# STM32F303CBT6_BTN8962TA_V1_0.net
KiCad netlist of a schematic drawn in EAGLE
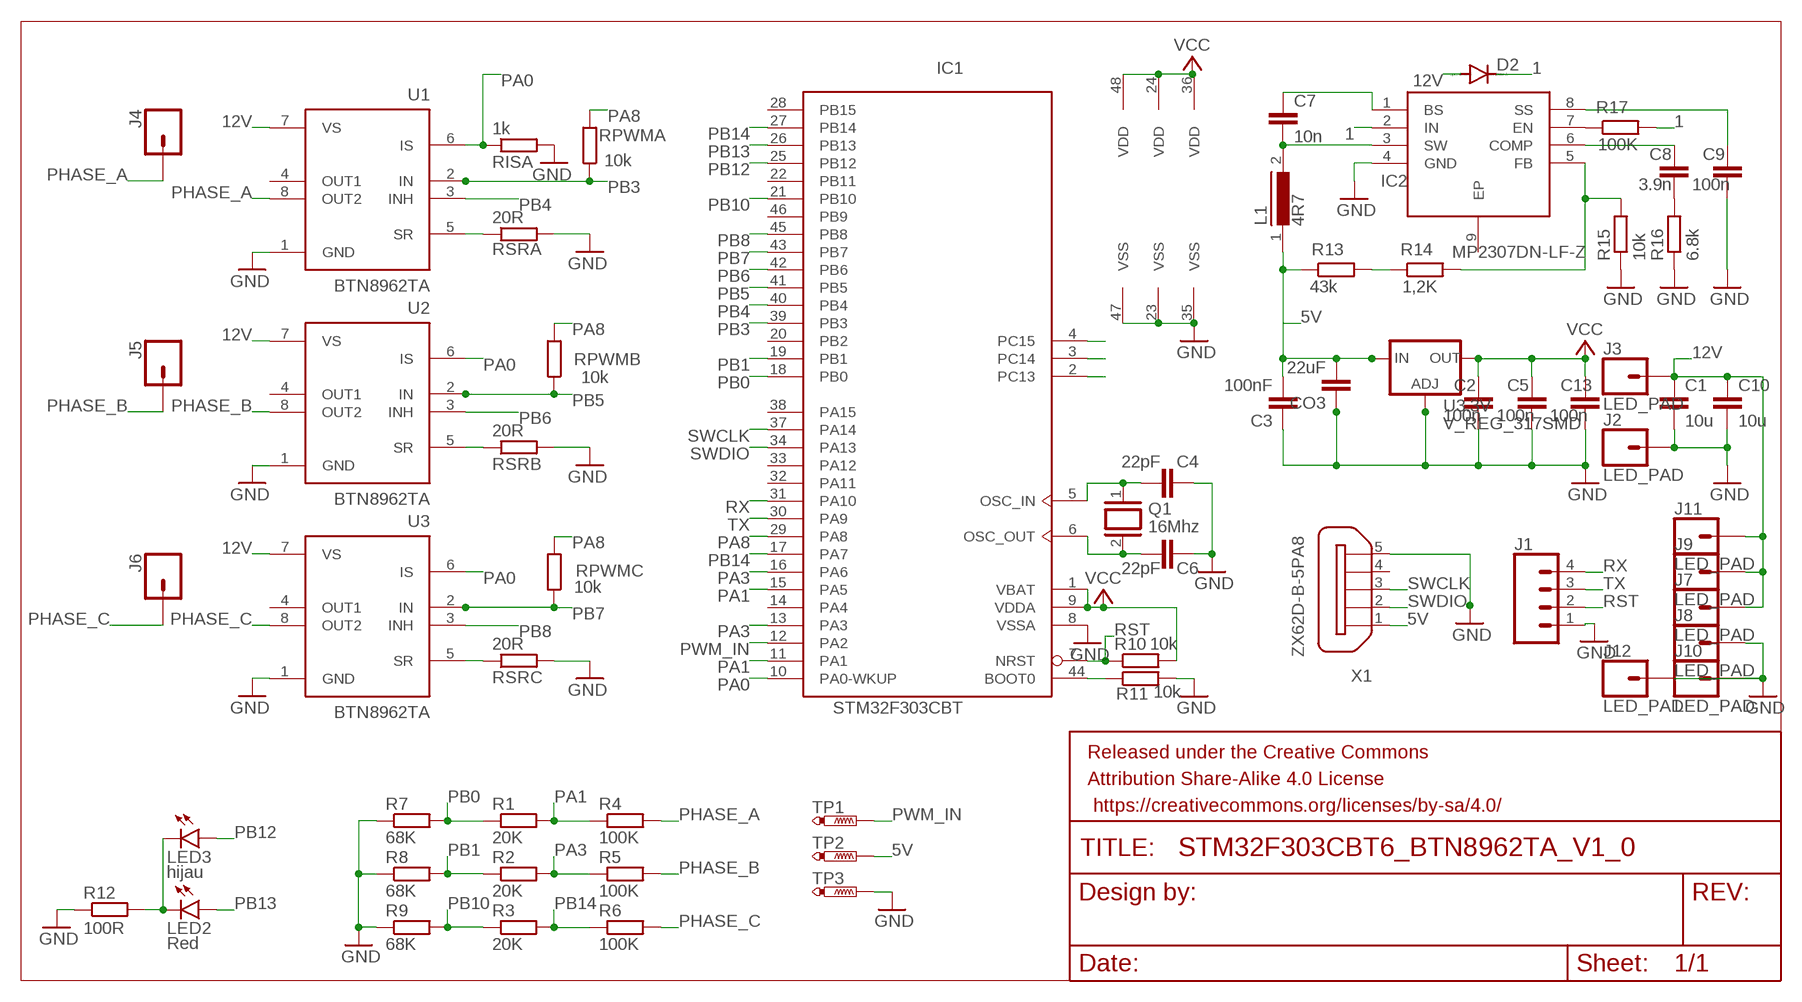
[diagram p0: schematic, sheet 1]

(export (version "E")
  (design (tool "Eeschema 10.0.6"))
  (components
    (comp (ref "C1")
      (value "10u")
      (footprint "eagle-import:C1206K")
      (libsource (lib "eagle-import") (part "rcl_334_C-EUC1206K"))
    )
    (comp (ref "C2")
      (value "100n")
      (footprint "eagle-import:C0603K")
      (libsource (lib "eagle-import") (part "rcl_334_C-EUC0603K"))
    )
    (comp (ref "C3")
      (value "100nF")
      (footprint "eagle-import:C0805")
      (libsource (lib "eagle-import") (part "C-EUC0805"))
    )
    (comp (ref "C4")
      (value "22pF")
      (footprint "eagle-import:C0805")
      (libsource (lib "eagle-import") (part "C-EUC0805"))
    )
    (comp (ref "C5")
      (value "100n")
      (footprint "eagle-import:C0603K")
      (libsource (lib "eagle-import") (part "rcl_334_C-EUC0603K"))
    )
    (comp (ref "C6")
      (value "22pF")
      (footprint "eagle-import:C0805")
      (libsource (lib "eagle-import") (part "C-EUC0805"))
    )
    (comp (ref "C7")
      (value "10n")
      (footprint "eagle-import:C0603K")
      (libsource (lib "eagle-import") (part "rcl_334_C-EUC0603K"))
    )
    (comp (ref "C8")
      (value "3.9n")
      (footprint "eagle-import:C0603K")
      (libsource (lib "eagle-import") (part "rcl_334_C-EUC0603K"))
    )
    (comp (ref "C9")
      (value "100n")
      (footprint "eagle-import:C0603K")
      (libsource (lib "eagle-import") (part "rcl_334_C-EUC0603K"))
    )
    (comp (ref "C10")
      (value "10u")
      (footprint "eagle-import:C1206K")
      (libsource (lib "eagle-import") (part "rcl_334_C-EUC1206K"))
    )
    (comp (ref "C13")
      (value "100n")
      (footprint "eagle-import:C0603K")
      (libsource (lib "eagle-import") (part "rcl_334_C-EUC0603K"))
    )
    (comp (ref "CO3")
      (value "22uF")
      (footprint "eagle-import:C0805")
      (libsource (lib "eagle-import") (part "C-EUC0805"))
    )
    (comp (ref "D2")
      (value "DIODE-SOD80C")
      (footprint "eagle-import:SOD80C")
      (libsource (lib "eagle-import") (part "DIODE-SOD80C"))
    )
    (comp (ref "FRAME1")
      (value "FRAME-LETTER")
      (footprint "eagle-import:CREATIVE_COMMONS")
      (libsource (lib "eagle-import") (part "FRAME-LETTER"))
    )
    (comp (ref "IC1")
      (value "STM32F303CBT")
      (footprint "eagle-import:LQFP48")
      (fields (field (name "SPICEPREFIX") "X"))
      (libsource (lib "eagle-import") (part "STM32F303CTB"))
    )
    (comp (ref "IC2")
      (value "MP2307DN-LF-Z")
      (footprint "eagle-import:SOIC127P600X170-9N")
      (fields (field (name "MOUSER_PART_NUMBER") "946-MP2307DNLFZ"))
      (libsource (lib "eagle-import") (part "MP2307DN-LF-Z"))
    )
    (comp (ref "J1")
      (value "CONN_04SMD2")
      (footprint "eagle-import:JST04_1MM_RA")
      (libsource (lib "eagle-import") (part "CONN_04SMD2"))
    )
    (comp (ref "J2")
      (value "LED_PAD")
      (footprint "eagle-import:CIRCULARPAD")
      (libsource (lib "eagle-import") (part "LED_PAD"))
    )
    (comp (ref "J3")
      (value "LED_PAD")
      (footprint "eagle-import:CIRCULARPAD")
      (libsource (lib "eagle-import") (part "LED_PAD"))
    )
    (comp (ref "J4")
      (value "CONN_01SNAP-MALE")
      (footprint "eagle-import:SNAP-MALE")
      (libsource (lib "eagle-import") (part "CONN_01SNAP-MALE"))
    )
    (comp (ref "J5")
      (value "CONN_01SNAP-MALE")
      (footprint "eagle-import:SNAP-MALE")
      (libsource (lib "eagle-import") (part "CONN_01SNAP-MALE"))
    )
    (comp (ref "J6")
      (value "CONN_01SNAP-MALE")
      (footprint "eagle-import:SNAP-MALE")
      (libsource (lib "eagle-import") (part "CONN_01SNAP-MALE"))
    )
    (comp (ref "J7")
      (value "LED_PAD")
      (footprint "eagle-import:CIRCULARPAD")
      (libsource (lib "eagle-import") (part "LED_PAD"))
    )
    (comp (ref "J8")
      (value "LED_PAD")
      (footprint "eagle-import:CIRCULARPAD")
      (libsource (lib "eagle-import") (part "LED_PAD"))
    )
    (comp (ref "J9")
      (value "LED_PAD")
      (footprint "eagle-import:CIRCULARPAD")
      (libsource (lib "eagle-import") (part "LED_PAD"))
    )
    (comp (ref "J10")
      (value "LED_PAD")
      (footprint "eagle-import:CIRCULARPAD")
      (libsource (lib "eagle-import") (part "LED_PAD"))
    )
    (comp (ref "J11")
      (value "LED_PAD")
      (footprint "eagle-import:CIRCULARPAD")
      (libsource (lib "eagle-import") (part "LED_PAD"))
    )
    (comp (ref "J12")
      (value "LED_PAD")
      (footprint "eagle-import:CIRCULARPAD")
      (libsource (lib "eagle-import") (part "LED_PAD"))
    )
    (comp (ref "L1")
      (value "4R7")
      (footprint "eagle-import:DR74")
      (libsource (lib "eagle-import") (part "DR74"))
    )
    (comp (ref "LED2")
      (value "Red")
      (footprint "eagle-import:CHIPLED_0805")
      (libsource (lib "eagle-import") (part "LEDCHIPLED_0805"))
    )
    (comp (ref "LED3")
      (value "hijau")
      (footprint "eagle-import:CHIPLED_0805")
      (libsource (lib "eagle-import") (part "LEDCHIPLED_0805"))
    )
    (comp (ref "Q1")
      (value "16Mhz")
      (footprint "eagle-import:QS")
      (libsource (lib "eagle-import") (part "XTAL/S"))
    )
    (comp (ref "R1")
      (value "20K")
      (footprint "eagle-import:R0805")
      (libsource (lib "eagle-import") (part "rcl_334_R-EU_R0805"))
    )
    (comp (ref "R2")
      (value "20K")
      (footprint "eagle-import:R0805")
      (libsource (lib "eagle-import") (part "rcl_334_R-EU_R0805"))
    )
    (comp (ref "R3")
      (value "20K")
      (footprint "eagle-import:R0805")
      (libsource (lib "eagle-import") (part "rcl_334_R-EU_R0805"))
    )
    (comp (ref "R4")
      (value "100K")
      (footprint "eagle-import:R0805")
      (libsource (lib "eagle-import") (part "rcl_334_R-EU_R0805"))
    )
    (comp (ref "R5")
      (value "100K")
      (footprint "eagle-import:R0805")
      (libsource (lib "eagle-import") (part "rcl_334_R-EU_R0805"))
    )
    (comp (ref "R6")
      (value "100K")
      (footprint "eagle-import:R0805")
      (libsource (lib "eagle-import") (part "rcl_334_R-EU_R0805"))
    )
    (comp (ref "R7")
      (value "68K")
      (footprint "eagle-import:R0805")
      (libsource (lib "eagle-import") (part "rcl_334_R-EU_R0805"))
    )
    (comp (ref "R8")
      (value "68K")
      (footprint "eagle-import:R0805")
      (libsource (lib "eagle-import") (part "rcl_334_R-EU_R0805"))
    )
    (comp (ref "R9")
      (value "68K")
      (footprint "eagle-import:R0805")
      (libsource (lib "eagle-import") (part "rcl_334_R-EU_R0805"))
    )
    (comp (ref "R10")
      (value "10k")
      (footprint "eagle-import:R0603")
      (libsource (lib "eagle-import") (part "rcl_334_R-EU_R0603"))
    )
    (comp (ref "R11")
      (value "10k")
      (footprint "eagle-import:R0603")
      (libsource (lib "eagle-import") (part "rcl_334_R-EU_R0603"))
    )
    (comp (ref "R12")
      (value "100R")
      (footprint "eagle-import:R0603")
      (libsource (lib "eagle-import") (part "rcl_334_R-EU_R0603"))
    )
    (comp (ref "R13")
      (value "43k")
      (footprint "eagle-import:R0603")
      (libsource (lib "eagle-import") (part "rcl_334_R-EU_R0603"))
    )
    (comp (ref "R14")
      (value "1,2K")
      (footprint "eagle-import:R0603")
      (libsource (lib "eagle-import") (part "rcl_334_R-EU_R0603"))
    )
    (comp (ref "R15")
      (value "10k")
      (footprint "eagle-import:R0603")
      (libsource (lib "eagle-import") (part "rcl_334_R-EU_R0603"))
    )
    (comp (ref "R16")
      (value "6.8k")
      (footprint "eagle-import:R0603")
      (libsource (lib "eagle-import") (part "rcl_334_R-EU_R0603"))
    )
    (comp (ref "R17")
      (value "100K")
      (footprint "eagle-import:R0603")
      (libsource (lib "eagle-import") (part "rcl_334_R-EU_R0603"))
    )
    (comp (ref "RISA")
      (value "1k")
      (footprint "eagle-import:R0805")
      (libsource (lib "eagle-import") (part "R-EU_R0805"))
    )
    (comp (ref "RPWMA")
      (value "10k")
      (footprint "eagle-import:R0805")
      (libsource (lib "eagle-import") (part "R-EU_R0805"))
    )
    (comp (ref "RPWMB")
      (value "10k")
      (footprint "eagle-import:R0805")
      (libsource (lib "eagle-import") (part "R-EU_R0805"))
    )
    (comp (ref "RPWMC")
      (value "10k")
      (footprint "eagle-import:R0805")
      (libsource (lib "eagle-import") (part "R-EU_R0805"))
    )
    (comp (ref "RSRA")
      (value "20R")
      (footprint "eagle-import:R0805")
      (libsource (lib "eagle-import") (part "rcl_334_R-EU_R0805"))
    )
    (comp (ref "RSRB")
      (value "20R")
      (footprint "eagle-import:R0805")
      (libsource (lib "eagle-import") (part "rcl_334_R-EU_R0805"))
    )
    (comp (ref "RSRC")
      (value "20R")
      (footprint "eagle-import:R0805")
      (libsource (lib "eagle-import") (part "rcl_334_R-EU_R0805"))
    )
    (comp (ref "TP1")
      (value "PTR1TP15SQ")
      (footprint "eagle-import:TP15SQ")
      (libsource (lib "eagle-import") (part "PTR1TP15SQ"))
    )
    (comp (ref "TP2")
      (value "PTR1TP15SQ")
      (footprint "eagle-import:TP15SQ")
      (libsource (lib "eagle-import") (part "PTR1TP15SQ"))
    )
    (comp (ref "TP3")
      (value "PTR1TP15SQ")
      (footprint "eagle-import:TP15SQ")
      (libsource (lib "eagle-import") (part "PTR1TP15SQ"))
    )
    (comp (ref "U1")
      (value "BTN8962TA")
      (footprint "eagle-import:TO127P1500X440-8N-1")
      (libsource (lib "eagle-import") (part "BTN8962TA"))
    )
    (comp (ref "U2")
      (value "BTN8962TA")
      (footprint "eagle-import:TO127P1500X440-8N-1")
      (libsource (lib "eagle-import") (part "BTN8962TA"))
    )
    (comp (ref "U3")
      (value "BTN8962TA")
      (footprint "eagle-import:TO127P1500X440-8N-1")
      (libsource (lib "eagle-import") (part "BTN8962TA"))
    )
    (comp (ref "U3.3V")
      (value "V_REG_317SMD")
      (footprint "eagle-import:SOT223")
      (libsource (lib "eagle-import") (part "V_REG_317SMD"))
    )
    (comp (ref "X1")
      (value "ZX62D-B-5PA8")
      (footprint "eagle-import:ZX62D-B-5PA8")
      (fields (field (name "MF") "Hirose"))
      (libsource (lib "eagle-import") (part "ZX62D-B-5PA8"))
    )
  )
  (nets
    (net (code "1") (name "/1") (class "Default")
      (node (ref "D2") (pin "C") (pinfunction "C_C") (pintype "passive"))
      (node (ref "IC2") (pin "2") (pinfunction "IN_2") (pintype "bidirectional"))
      (node (ref "R17") (pin "2") (pinfunction "2_2") (pintype "passive"))
    )
    (net (code "2") (name "/5V") (class "Default")
      (node (ref "C3") (pin "2") (pinfunction "2_2") (pintype "passive"))
      (node (ref "CO3") (pin "2") (pinfunction "2_2") (pintype "passive"))
      (node (ref "L1") (pin "1") (pinfunction "1_1") (pintype "passive"))
      (node (ref "R13") (pin "1") (pinfunction "1_1") (pintype "passive"))
      (node (ref "TP2") (pin "TP") (pinfunction "TP_TP") (pintype "input"))
      (node (ref "U3.3V") (pin "3") (pinfunction "IN_3") (pintype "input"))
      (node (ref "X1") (pin "1") (pinfunction "1_1") (pintype "passive"))
    )
    (net (code "3") (name "/12V") (class "Default")
      (node (ref "C1") (pin "1") (pinfunction "1_1") (pintype "passive"))
      (node (ref "C10") (pin "1") (pinfunction "1_1") (pintype "passive"))
      (node (ref "D2") (pin "A") (pinfunction "A_A") (pintype "passive"))
      (node (ref "J11") (pin "P$1") (pinfunction "1_P$1") (pintype "passive"))
      (node (ref "J11") (pin "P$2") (pinfunction "1_P$2") (pintype "passive"))
      (node (ref "J3") (pin "P$1") (pinfunction "1_P$1") (pintype "passive"))
      (node (ref "J3") (pin "P$2") (pinfunction "1_P$2") (pintype "passive"))
      (node (ref "J7") (pin "P$1") (pinfunction "1_P$1") (pintype "passive"))
      (node (ref "J7") (pin "P$2") (pinfunction "1_P$2") (pintype "passive"))
      (node (ref "J9") (pin "P$1") (pinfunction "1_P$1") (pintype "passive"))
      (node (ref "J9") (pin "P$2") (pinfunction "1_P$2") (pintype "passive"))
      (node (ref "U1") (pin "7") (pinfunction "VS_7") (pintype "power_in"))
      (node (ref "U2") (pin "7") (pinfunction "VS_7") (pintype "power_in"))
      (node (ref "U3") (pin "7") (pinfunction "VS_7") (pintype "power_in"))
    )
    (net (code "4") (name "/PA0") (class "Default")
      (node (ref "IC1") (pin "10") (pinfunction "PA0-WKUP_10") (pintype "bidirectional"))
      (node (ref "RISA") (pin "1") (pinfunction "1_1") (pintype "passive"))
      (node (ref "U1") (pin "6") (pinfunction "IS_6") (pintype "output"))
      (node (ref "U2") (pin "6") (pinfunction "IS_6") (pintype "output"))
      (node (ref "U3") (pin "6") (pinfunction "IS_6") (pintype "output"))
    )
    (net (code "5") (name "/PA1") (class "Default")
      (node (ref "IC1") (pin "11") (pinfunction "PA1_11") (pintype "bidirectional"))
      (node (ref "IC1") (pin "15") (pinfunction "PA5_15") (pintype "bidirectional"))
      (node (ref "R1") (pin "2") (pinfunction "2_2") (pintype "passive"))
      (node (ref "R4") (pin "1") (pinfunction "1_1") (pintype "passive"))
    )
    (net (code "6") (name "/PA3") (class "Default")
      (node (ref "IC1") (pin "13") (pinfunction "PA3_13") (pintype "bidirectional"))
      (node (ref "IC1") (pin "16") (pinfunction "PA6_16") (pintype "bidirectional"))
      (node (ref "R2") (pin "2") (pinfunction "2_2") (pintype "passive"))
      (node (ref "R5") (pin "1") (pinfunction "1_1") (pintype "passive"))
    )
    (net (code "7") (name "/PA8") (class "Default")
      (node (ref "IC1") (pin "29") (pinfunction "PA8_29") (pintype "bidirectional"))
      (node (ref "RPWMA") (pin "2") (pinfunction "2_2") (pintype "passive"))
      (node (ref "RPWMB") (pin "2") (pinfunction "2_2") (pintype "passive"))
      (node (ref "RPWMC") (pin "2") (pinfunction "2_2") (pintype "passive"))
    )
    (net (code "8") (name "/PB0") (class "Default")
      (node (ref "IC1") (pin "18") (pinfunction "PB0_18") (pintype "bidirectional"))
      (node (ref "R1") (pin "1") (pinfunction "1_1") (pintype "passive"))
      (node (ref "R7") (pin "2") (pinfunction "2_2") (pintype "passive"))
    )
    (net (code "9") (name "/PB1") (class "Default")
      (node (ref "IC1") (pin "19") (pinfunction "PB1_19") (pintype "bidirectional"))
      (node (ref "R2") (pin "1") (pinfunction "1_1") (pintype "passive"))
      (node (ref "R8") (pin "2") (pinfunction "2_2") (pintype "passive"))
    )
    (net (code "10") (name "/PB3") (class "Default")
      (node (ref "IC1") (pin "39") (pinfunction "PB3_39") (pintype "bidirectional"))
      (node (ref "RPWMA") (pin "1") (pinfunction "1_1") (pintype "passive"))
      (node (ref "U1") (pin "2") (pinfunction "IN_2") (pintype "input"))
    )
    (net (code "11") (name "/PB4") (class "Default")
      (node (ref "IC1") (pin "40") (pinfunction "PB4_40") (pintype "bidirectional"))
      (node (ref "U1") (pin "3") (pinfunction "INH_3") (pintype "input"))
    )
    (net (code "12") (name "/PB5") (class "Default")
      (node (ref "IC1") (pin "41") (pinfunction "PB5_41") (pintype "bidirectional"))
      (node (ref "RPWMB") (pin "1") (pinfunction "1_1") (pintype "passive"))
      (node (ref "U2") (pin "2") (pinfunction "IN_2") (pintype "input"))
    )
    (net (code "13") (name "/PB6") (class "Default")
      (node (ref "IC1") (pin "42") (pinfunction "PB6_42") (pintype "bidirectional"))
      (node (ref "U2") (pin "3") (pinfunction "INH_3") (pintype "input"))
    )
    (net (code "14") (name "/PB7") (class "Default")
      (node (ref "IC1") (pin "43") (pinfunction "PB7_43") (pintype "bidirectional"))
      (node (ref "RPWMC") (pin "1") (pinfunction "1_1") (pintype "passive"))
      (node (ref "U3") (pin "2") (pinfunction "IN_2") (pintype "input"))
    )
    (net (code "15") (name "/PB8") (class "Default")
      (node (ref "IC1") (pin "45") (pinfunction "PB8_45") (pintype "bidirectional"))
      (node (ref "U3") (pin "3") (pinfunction "INH_3") (pintype "input"))
    )
    (net (code "16") (name "/PB10") (class "Default")
      (node (ref "IC1") (pin "21") (pinfunction "PB10_21") (pintype "bidirectional"))
      (node (ref "R3") (pin "1") (pinfunction "1_1") (pintype "passive"))
      (node (ref "R9") (pin "2") (pinfunction "2_2") (pintype "passive"))
    )
    (net (code "17") (name "/PB12") (class "Default")
      (node (ref "IC1") (pin "25") (pinfunction "PB12_25") (pintype "bidirectional"))
      (node (ref "LED3") (pin "A") (pinfunction "A_A") (pintype "passive"))
    )
    (net (code "18") (name "/PB13") (class "Default")
      (node (ref "IC1") (pin "26") (pinfunction "PB13_26") (pintype "bidirectional"))
      (node (ref "LED2") (pin "A") (pinfunction "A_A") (pintype "passive"))
    )
    (net (code "19") (name "/PB14") (class "Default")
      (node (ref "IC1") (pin "17") (pinfunction "PA7_17") (pintype "bidirectional"))
      (node (ref "IC1") (pin "27") (pinfunction "PB14_27") (pintype "bidirectional"))
      (node (ref "R3") (pin "2") (pinfunction "2_2") (pintype "passive"))
      (node (ref "R6") (pin "1") (pinfunction "1_1") (pintype "passive"))
    )
    (net (code "20") (name "/PHASE_A") (class "Default")
      (node (ref "J4") (pin "2") (pinfunction "1_2") (pintype "passive"))
      (node (ref "R4") (pin "2") (pinfunction "2_2") (pintype "passive"))
      (node (ref "U1") (pin "8") (pinfunction "OUT2_8") (pintype "output"))
    )
    (net (code "21") (name "/PHASE_B") (class "Default")
      (node (ref "J5") (pin "2") (pinfunction "1_2") (pintype "passive"))
      (node (ref "R5") (pin "2") (pinfunction "2_2") (pintype "passive"))
      (node (ref "U2") (pin "8") (pinfunction "OUT2_8") (pintype "output"))
    )
    (net (code "22") (name "/PHASE_C") (class "Default")
      (node (ref "J6") (pin "2") (pinfunction "1_2") (pintype "passive"))
      (node (ref "R6") (pin "2") (pinfunction "2_2") (pintype "passive"))
      (node (ref "U3") (pin "8") (pinfunction "OUT2_8") (pintype "output"))
    )
    (net (code "23") (name "/PWM_IN") (class "Default")
      (node (ref "IC1") (pin "12") (pinfunction "PA2_12") (pintype "bidirectional"))
      (node (ref "TP1") (pin "TP") (pinfunction "TP_TP") (pintype "input"))
    )
    (net (code "24") (name "/RST") (class "Default")
      (node (ref "IC1") (pin "7") (pinfunction "NRST_7") (pintype "bidirectional"))
      (node (ref "J1") (pin "2") (pinfunction "2_2") (pintype "passive"))
      (node (ref "R10") (pin "1") (pinfunction "1_1") (pintype "passive"))
    )
    (net (code "25") (name "/RX") (class "Default")
      (node (ref "IC1") (pin "31") (pinfunction "PA10_31") (pintype "bidirectional"))
      (node (ref "J1") (pin "4") (pinfunction "4_4") (pintype "passive"))
    )
    (net (code "26") (name "/SWCLK") (class "Default")
      (node (ref "IC1") (pin "37") (pinfunction "PA14_37") (pintype "bidirectional"))
      (node (ref "X1") (pin "3") (pinfunction "3_3") (pintype "passive"))
    )
    (net (code "27") (name "/SWDIO") (class "Default")
      (node (ref "IC1") (pin "34") (pinfunction "PA13_34") (pintype "bidirectional"))
      (node (ref "X1") (pin "2") (pinfunction "2_2") (pintype "passive"))
    )
    (net (code "28") (name "/TX") (class "Default")
      (node (ref "IC1") (pin "30") (pinfunction "PA9_30") (pintype "bidirectional"))
      (node (ref "J1") (pin "3") (pinfunction "3_3") (pintype "passive"))
    )
    (net (code "29") (name "GND") (class "Default")
      (node (ref "C1") (pin "2") (pinfunction "2_2") (pintype "passive"))
      (node (ref "C10") (pin "2") (pinfunction "2_2") (pintype "passive"))
      (node (ref "C13") (pin "2") (pinfunction "2_2") (pintype "passive"))
      (node (ref "C2") (pin "2") (pinfunction "2_2") (pintype "passive"))
      (node (ref "C3") (pin "1") (pinfunction "1_1") (pintype "passive"))
      (node (ref "C4") (pin "1") (pinfunction "1_1") (pintype "passive"))
      (node (ref "C5") (pin "2") (pinfunction "2_2") (pintype "passive"))
      (node (ref "C6") (pin "1") (pinfunction "1_1") (pintype "passive"))
      (node (ref "C9") (pin "2") (pinfunction "2_2") (pintype "passive"))
      (node (ref "CO3") (pin "1") (pinfunction "1_1") (pintype "passive"))
      (node (ref "IC1") (pin "23") (pinfunction "VSS_23") (pintype "power_in"))
      (node (ref "IC1") (pin "35") (pinfunction "VSS_35") (pintype "power_in"))
      (node (ref "IC1") (pin "47") (pinfunction "VSS_47") (pintype "power_in"))
      (node (ref "IC1") (pin "8") (pinfunction "VSSA_8") (pintype "power_in"))
      (node (ref "IC2") (pin "4") (pinfunction "GND_4") (pintype "bidirectional"))
      (node (ref "J1") (pin "1") (pinfunction "1_1") (pintype "passive"))
      (node (ref "J10") (pin "P$1") (pinfunction "1_P$1") (pintype "passive"))
      (node (ref "J10") (pin "P$2") (pinfunction "1_P$2") (pintype "passive"))
      (node (ref "J12") (pin "P$1") (pinfunction "1_P$1") (pintype "passive"))
      (node (ref "J12") (pin "P$2") (pinfunction "1_P$2") (pintype "passive"))
      (node (ref "J2") (pin "P$1") (pinfunction "1_P$1") (pintype "passive"))
      (node (ref "J2") (pin "P$2") (pinfunction "1_P$2") (pintype "passive"))
      (node (ref "J8") (pin "P$1") (pinfunction "1_P$1") (pintype "passive"))
      (node (ref "J8") (pin "P$2") (pinfunction "1_P$2") (pintype "passive"))
      (node (ref "R11") (pin "2") (pinfunction "2_2") (pintype "passive"))
      (node (ref "R12") (pin "1") (pinfunction "1_1") (pintype "passive"))
      (node (ref "R15") (pin "1") (pinfunction "1_1") (pintype "passive"))
      (node (ref "R16") (pin "1") (pinfunction "1_1") (pintype "passive"))
      (node (ref "R7") (pin "1") (pinfunction "1_1") (pintype "passive"))
      (node (ref "R8") (pin "1") (pinfunction "1_1") (pintype "passive"))
      (node (ref "R9") (pin "1") (pinfunction "1_1") (pintype "passive"))
      (node (ref "RISA") (pin "2") (pinfunction "2_2") (pintype "passive"))
      (node (ref "RSRA") (pin "2") (pinfunction "2_2") (pintype "passive"))
      (node (ref "RSRB") (pin "2") (pinfunction "2_2") (pintype "passive"))
      (node (ref "RSRC") (pin "2") (pinfunction "2_2") (pintype "passive"))
      (node (ref "TP3") (pin "TP") (pinfunction "TP_TP") (pintype "input"))
      (node (ref "U1") (pin "1") (pinfunction "GND_1") (pintype "power_in"))
      (node (ref "U2") (pin "1") (pinfunction "GND_1") (pintype "power_in"))
      (node (ref "U3") (pin "1") (pinfunction "GND_1") (pintype "power_in"))
      (node (ref "U3.3V") (pin "1") (pinfunction "ADJ_1") (pintype "input"))
      (node (ref "X1") (pin "5") (pinfunction "5_5") (pintype "passive"))
    )
    (net (code "30") (name "Net-(C8-Pad2)") (class "Default")
      (node (ref "C8") (pin "2") (pinfunction "2_2") (pintype "passive"))
      (node (ref "R16") (pin "2") (pinfunction "2_2") (pintype "passive"))
    )
    (net (code "31") (name "Net-(IC1A-BOOT0)") (class "Default")
      (node (ref "IC1") (pin "44") (pinfunction "BOOT0_44") (pintype "input"))
      (node (ref "R11") (pin "1") (pinfunction "1_1") (pintype "passive"))
    )
    (net (code "32") (name "Net-(IC1A-OSC_IN)") (class "Default")
      (node (ref "C4") (pin "2") (pinfunction "2_2") (pintype "passive"))
      (node (ref "IC1") (pin "5") (pinfunction "OSC_IN_5") (pintype "bidirectional"))
      (node (ref "Q1") (pin "1") (pinfunction "1_1") (pintype "passive"))
    )
    (net (code "33") (name "Net-(IC1A-OSC_OUT)") (class "Default")
      (node (ref "C6") (pin "2") (pinfunction "2_2") (pintype "passive"))
      (node (ref "IC1") (pin "6") (pinfunction "OSC_OUT_6") (pintype "bidirectional"))
      (node (ref "Q1") (pin "2") (pinfunction "2_2") (pintype "passive"))
    )
    (net (code "34") (name "Net-(IC2-BS)") (class "Default")
      (node (ref "C7") (pin "1") (pinfunction "1_1") (pintype "passive"))
      (node (ref "IC2") (pin "1") (pinfunction "BS_1") (pintype "bidirectional"))
    )
    (net (code "35") (name "Net-(IC2-COMP)") (class "Default")
      (node (ref "C8") (pin "1") (pinfunction "1_1") (pintype "passive"))
      (node (ref "IC2") (pin "6") (pinfunction "COMP_6") (pintype "bidirectional"))
    )
    (net (code "36") (name "Net-(IC2-EN)") (class "Default")
      (node (ref "IC2") (pin "7") (pinfunction "EN_7") (pintype "bidirectional"))
      (node (ref "R17") (pin "1") (pinfunction "1_1") (pintype "passive"))
    )
    (net (code "37") (name "Net-(IC2-FB)") (class "Default")
      (node (ref "IC2") (pin "5") (pinfunction "FB_5") (pintype "bidirectional"))
      (node (ref "R14") (pin "2") (pinfunction "2_2") (pintype "passive"))
      (node (ref "R15") (pin "2") (pinfunction "2_2") (pintype "passive"))
    )
    (net (code "38") (name "Net-(IC2-SS)") (class "Default")
      (node (ref "C9") (pin "1") (pinfunction "1_1") (pintype "passive"))
      (node (ref "IC2") (pin "8") (pinfunction "SS_8") (pintype "bidirectional"))
    )
    (net (code "39") (name "Net-(IC2-SW)") (class "Default")
      (node (ref "C7") (pin "2") (pinfunction "2_2") (pintype "passive"))
      (node (ref "IC2") (pin "3") (pinfunction "SW_3") (pintype "bidirectional"))
      (node (ref "L1") (pin "2") (pinfunction "2_2") (pintype "passive"))
    )
    (net (code "40") (name "Net-(LED2-PadC)") (class "Default")
      (node (ref "LED2") (pin "C") (pinfunction "C_C") (pintype "passive"))
      (node (ref "LED3") (pin "C") (pinfunction "C_C") (pintype "passive"))
      (node (ref "R12") (pin "2") (pinfunction "2_2") (pintype "passive"))
    )
    (net (code "41") (name "Net-(R13-Pad2)") (class "Default")
      (node (ref "R13") (pin "2") (pinfunction "2_2") (pintype "passive"))
      (node (ref "R14") (pin "1") (pinfunction "1_1") (pintype "passive"))
    )
    (net (code "42") (name "Net-(U1-SR)") (class "Default")
      (node (ref "RSRA") (pin "1") (pinfunction "1_1") (pintype "passive"))
      (node (ref "U1") (pin "5") (pinfunction "SR_5") (pintype "input"))
    )
    (net (code "43") (name "Net-(U2-SR)") (class "Default")
      (node (ref "RSRB") (pin "1") (pinfunction "1_1") (pintype "passive"))
      (node (ref "U2") (pin "5") (pinfunction "SR_5") (pintype "input"))
    )
    (net (code "44") (name "Net-(U3-SR)") (class "Default")
      (node (ref "RSRC") (pin "1") (pinfunction "1_1") (pintype "passive"))
      (node (ref "U3") (pin "5") (pinfunction "SR_5") (pintype "input"))
    )
    (net (code "45") (name "VCC") (class "Default")
      (node (ref "C13") (pin "1") (pinfunction "1_1") (pintype "passive"))
      (node (ref "C2") (pin "1") (pinfunction "1_1") (pintype "passive"))
      (node (ref "C5") (pin "1") (pinfunction "1_1") (pintype "passive"))
      (node (ref "IC1") (pin "1") (pinfunction "VBAT_1") (pintype "power_in"))
      (node (ref "IC1") (pin "24") (pinfunction "VDD_24") (pintype "power_in"))
      (node (ref "IC1") (pin "36") (pinfunction "VDD_36") (pintype "power_in"))
      (node (ref "IC1") (pin "48") (pinfunction "VDD_48") (pintype "power_in"))
      (node (ref "IC1") (pin "9") (pinfunction "VDDA_9") (pintype "power_in"))
      (node (ref "R10") (pin "2") (pinfunction "2_2") (pintype "passive"))
      (node (ref "U3.3V") (pin "2") (pinfunction "OUT_2") (pintype "output"))
    )
    (net (code "46") (name "unconnected-(IC1A-PA4-Pad14)") (class "Default")
      (node (ref "IC1") (pin "14") (pinfunction "PA4_14") (pintype "bidirectional"))
    )
    (net (code "47") (name "unconnected-(IC1A-PA11-Pad32)") (class "Default")
      (node (ref "IC1") (pin "32") (pinfunction "PA11_32") (pintype "bidirectional"))
    )
    (net (code "48") (name "unconnected-(IC1A-PA12-Pad33)") (class "Default")
      (node (ref "IC1") (pin "33") (pinfunction "PA12_33") (pintype "bidirectional"))
    )
    (net (code "49") (name "unconnected-(IC1A-PA15-Pad38)") (class "Default")
      (node (ref "IC1") (pin "38") (pinfunction "PA15_38") (pintype "bidirectional"))
    )
    (net (code "50") (name "unconnected-(IC1A-PB2-Pad20)") (class "Default")
      (node (ref "IC1") (pin "20") (pinfunction "PB2_20") (pintype "bidirectional"))
    )
    (net (code "51") (name "unconnected-(IC1A-PB9-Pad46)") (class "Default")
      (node (ref "IC1") (pin "46") (pinfunction "PB9_46") (pintype "bidirectional"))
    )
    (net (code "52") (name "unconnected-(IC1A-PB11-Pad22)") (class "Default")
      (node (ref "IC1") (pin "22") (pinfunction "PB11_22") (pintype "bidirectional"))
    )
    (net (code "53") (name "unconnected-(IC1A-PB15-Pad28)") (class "Default")
      (node (ref "IC1") (pin "28") (pinfunction "PB15_28") (pintype "bidirectional"))
    )
    (net (code "54") (name "unconnected-(IC1A-PC13-Pad2)") (class "Default")
      (node (ref "IC1") (pin "2") (pinfunction "PC13_2") (pintype "bidirectional"))
    )
    (net (code "55") (name "unconnected-(IC1A-PC14-Pad3)") (class "Default")
      (node (ref "IC1") (pin "3") (pinfunction "PC14_3") (pintype "bidirectional"))
    )
    (net (code "56") (name "unconnected-(IC1A-PC15-Pad4)") (class "Default")
      (node (ref "IC1") (pin "4") (pinfunction "PC15_4") (pintype "bidirectional"))
    )
    (net (code "57") (name "unconnected-(IC2-EP-Pad9)") (class "Default")
      (node (ref "IC2") (pin "9") (pinfunction "EP_9") (pintype "bidirectional"))
    )
    (net (code "58") (name "unconnected-(U1-OUT1-Pad4)") (class "Default")
      (node (ref "U1") (pin "4") (pinfunction "OUT1_4") (pintype "output"))
    )
    (net (code "59") (name "unconnected-(U2-OUT1-Pad4)") (class "Default")
      (node (ref "U2") (pin "4") (pinfunction "OUT1_4") (pintype "output"))
    )
    (net (code "60") (name "unconnected-(U3-OUT1-Pad4)") (class "Default")
      (node (ref "U3") (pin "4") (pinfunction "OUT1_4") (pintype "output"))
    )
    (net (code "61") (name "unconnected-(X1-Pad4)") (class "Default")
      (node (ref "X1") (pin "4") (pinfunction "4_4") (pintype "passive"))
    )
  )
)
